# nRF52840_qfaa_var1.net
KiCad netlist of a schematic drawn in EAGLE
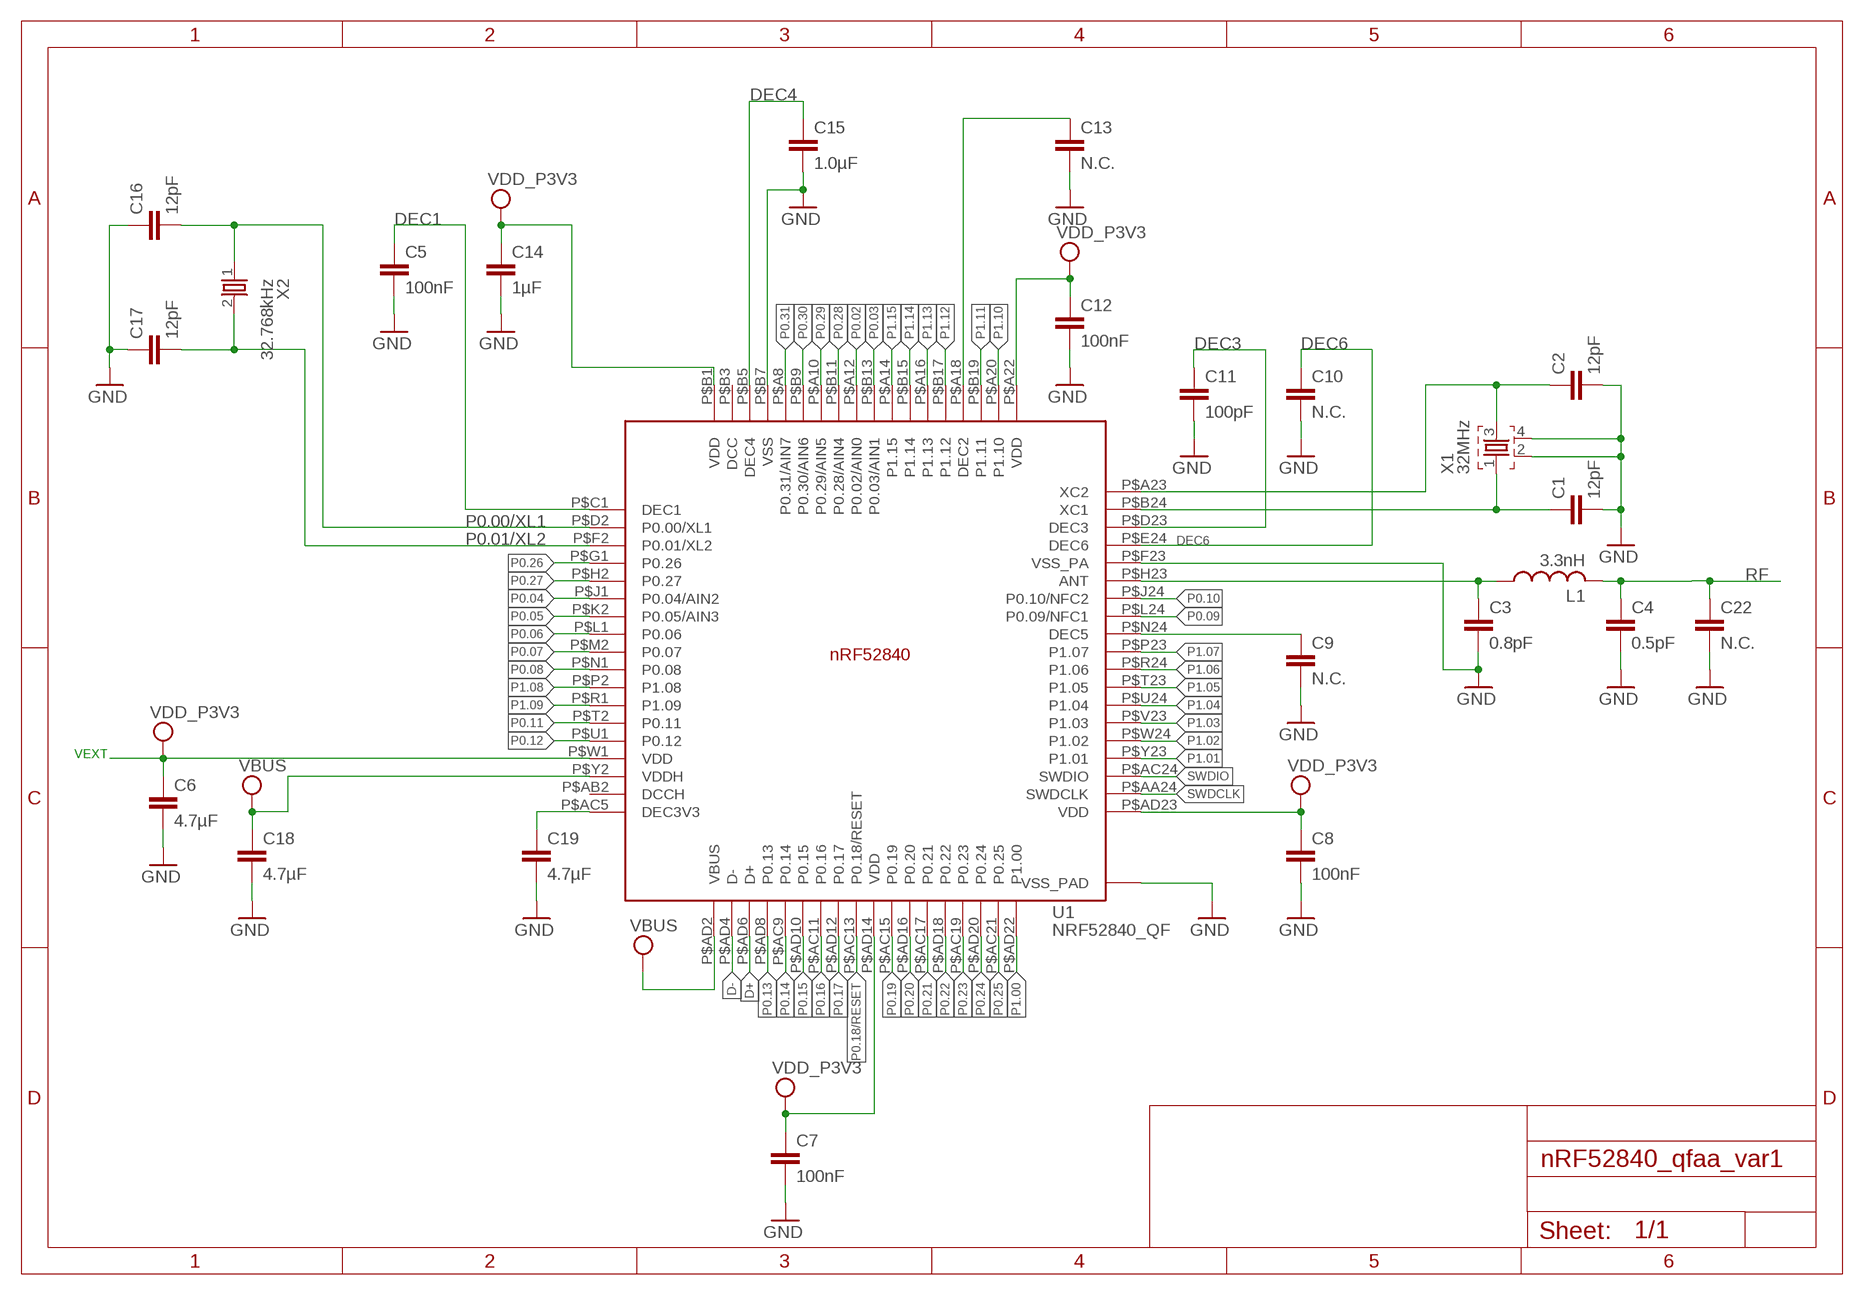
[diagram p0: schematic, sheet 1]

(export (version "E")
  (design (tool "Eeschema 10.0.6"))
  (components
    (comp (ref "C1")
      (value "12pF")
      (footprint "eagle-import:RESC0402_N")
      (libsource (lib "eagle-import") (part "CAPACITOR_0402_N"))
    )
    (comp (ref "C2")
      (value "12pF")
      (footprint "eagle-import:RESC0402_N")
      (libsource (lib "eagle-import") (part "CAPACITOR_0402_N"))
    )
    (comp (ref "C3")
      (value "0.8pF")
      (footprint "eagle-import:RESC0402_N")
      (libsource (lib "eagle-import") (part "CAPACITOR_0402_N"))
    )
    (comp (ref "C4")
      (value "0.5pF")
      (footprint "eagle-import:RESC0402_N")
      (libsource (lib "eagle-import") (part "CAPACITOR_0402_N"))
    )
    (comp (ref "C5")
      (value "100nF")
      (footprint "eagle-import:RESC0402_N")
      (libsource (lib "eagle-import") (part "CAPACITOR_0402_N"))
    )
    (comp (ref "C6")
      (value "4.7µF")
      (footprint "eagle-import:RESC0603_N")
      (libsource (lib "eagle-import") (part "CAPACITOR_0603_N"))
    )
    (comp (ref "C7")
      (value "100nF")
      (footprint "eagle-import:RESC0402_N")
      (libsource (lib "eagle-import") (part "CAPACITOR_0402_N"))
    )
    (comp (ref "C8")
      (value "100nF")
      (footprint "eagle-import:RESC0402_N")
      (libsource (lib "eagle-import") (part "CAPACITOR_0402_N"))
    )
    (comp (ref "C9")
      (value "N.C.")
      (footprint "eagle-import:RESC0402_N")
      (libsource (lib "eagle-import") (part "CAPACITOR_0402_N"))
    )
    (comp (ref "C10")
      (value "N.C.")
      (footprint "eagle-import:RESC0402_N")
      (libsource (lib "eagle-import") (part "CAPACITOR_0402_N"))
    )
    (comp (ref "C11")
      (value "100pF")
      (footprint "eagle-import:RESC0402_N")
      (libsource (lib "eagle-import") (part "CAPACITOR_0402_N"))
    )
    (comp (ref "C12")
      (value "100nF")
      (footprint "eagle-import:RESC0402_N")
      (libsource (lib "eagle-import") (part "CAPACITOR_0402_N"))
    )
    (comp (ref "C13")
      (value "N.C.")
      (footprint "eagle-import:RESC0402_N")
      (libsource (lib "eagle-import") (part "CAPACITOR_0402_N"))
    )
    (comp (ref "C14")
      (value "1µF")
      (footprint "eagle-import:RESC0603_N")
      (libsource (lib "eagle-import") (part "CAPACITOR_0603_N"))
    )
    (comp (ref "C15")
      (value "1.0µF")
      (footprint "eagle-import:RESC0603_N")
      (libsource (lib "eagle-import") (part "CAPACITOR_0603_N"))
    )
    (comp (ref "C16")
      (value "12pF")
      (footprint "eagle-import:RESC0402_N")
      (libsource (lib "eagle-import") (part "CAPACITOR_0402_N"))
    )
    (comp (ref "C17")
      (value "12pF")
      (footprint "eagle-import:RESC0402_N")
      (libsource (lib "eagle-import") (part "CAPACITOR_0402_N"))
    )
    (comp (ref "C18")
      (value "4.7µF")
      (footprint "eagle-import:RESC0603_N")
      (libsource (lib "eagle-import") (part "CAPACITOR_0603_N"))
    )
    (comp (ref "C19")
      (value "4.7µF")
      (footprint "eagle-import:RESC0603_N")
      (libsource (lib "eagle-import") (part "CAPACITOR_0603_N"))
    )
    (comp (ref "C22")
      (value "N.C.")
      (footprint "eagle-import:RESC0402_N")
      (libsource (lib "eagle-import") (part "CAPACITOR_0402_N"))
    )
    (comp (ref "L1")
      (value "3.3nH")
      (footprint "eagle-import:RESC0402_N")
      (libsource (lib "eagle-import") (part "INDUCTOR_0402_N"))
    )
    (comp (ref "U1")
      (value "NRF52840_QF")
      (footprint "eagle-import:AQFN50P700X700X85_HS-74N")
      (libsource (lib "eagle-import") (part "NRF52840_QF"))
    )
    (comp (ref "X1")
      (value "32MHz")
      (footprint "eagle-import:BT-XTAL_2016_N")
      (libsource (lib "eagle-import") (part "XTAL_32MHZ"))
    )
    (comp (ref "X2")
      (value "32.768kHz")
      (footprint "eagle-import:XTAL_3215_N")
      (libsource (lib "eagle-import") (part "XTAL_32KHZ"))
    )
  )
  (nets
    (net (code "1") (name "/DEC1") (class "Default")
      (node (ref "C5") (pin "1") (pinfunction "1_1") (pintype "passive"))
      (node (ref "U1") (pin "P$C1") (pinfunction "DEC1_P$C1") (pintype "power_in"))
    )
    (net (code "2") (name "/DEC3") (class "Default")
      (node (ref "C11") (pin "1") (pinfunction "1_1") (pintype "passive"))
      (node (ref "U1") (pin "P$D23") (pinfunction "DEC3_P$D23") (pintype "bidirectional"))
    )
    (net (code "3") (name "/DEC4") (class "Default")
      (node (ref "C15") (pin "1") (pinfunction "1_1") (pintype "passive"))
      (node (ref "U1") (pin "P$B5") (pinfunction "DEC4_P$B5") (pintype "power_in"))
    )
    (net (code "4") (name "/DEC6") (class "Default")
      (node (ref "C10") (pin "1") (pinfunction "1_1") (pintype "passive"))
      (node (ref "U1") (pin "P$E24") (pinfunction "DEC6_P$E24") (pintype "bidirectional"))
    )
    (net (code "5") (name "/P0.00{slash}XL1") (class "Default")
      (node (ref "C16") (pin "2") (pinfunction "2_2") (pintype "passive"))
      (node (ref "U1") (pin "P$D2") (pinfunction "P0.00/XL1_P$D2") (pintype "bidirectional"))
      (node (ref "X2") (pin "1") (pinfunction "1_1") (pintype "passive"))
    )
    (net (code "6") (name "/P0.01{slash}XL2") (class "Default")
      (node (ref "C17") (pin "2") (pinfunction "2_2") (pintype "passive"))
      (node (ref "U1") (pin "P$F2") (pinfunction "P0.01/XL2_P$F2") (pintype "bidirectional"))
      (node (ref "X2") (pin "2") (pinfunction "2_2") (pintype "passive"))
    )
    (net (code "7") (name "/RF") (class "Default")
      (node (ref "C22") (pin "1") (pinfunction "1_1") (pintype "passive"))
      (node (ref "C4") (pin "1") (pinfunction "1_1") (pintype "passive"))
      (node (ref "L1") (pin "2") (pinfunction "2_2") (pintype "passive"))
    )
    (net (code "8") (name "D+") (class "Default")
      (node (ref "U1") (pin "P$AD6") (pinfunction "D+_P$AD6") (pintype "bidirectional"))
    )
    (net (code "9") (name "D-") (class "Default")
      (node (ref "U1") (pin "P$AD4") (pinfunction "D-_P$AD4") (pintype "bidirectional"))
    )
    (net (code "10") (name "GND") (class "Default")
      (node (ref "C1") (pin "2") (pinfunction "2_2") (pintype "passive"))
      (node (ref "C10") (pin "2") (pinfunction "2_2") (pintype "passive"))
      (node (ref "C11") (pin "2") (pinfunction "2_2") (pintype "passive"))
      (node (ref "C12") (pin "2") (pinfunction "2_2") (pintype "passive"))
      (node (ref "C13") (pin "2") (pinfunction "2_2") (pintype "passive"))
      (node (ref "C14") (pin "2") (pinfunction "2_2") (pintype "passive"))
      (node (ref "C15") (pin "2") (pinfunction "2_2") (pintype "passive"))
      (node (ref "C16") (pin "1") (pinfunction "1_1") (pintype "passive"))
      (node (ref "C17") (pin "1") (pinfunction "1_1") (pintype "passive"))
      (node (ref "C18") (pin "2") (pinfunction "2_2") (pintype "passive"))
      (node (ref "C19") (pin "2") (pinfunction "2_2") (pintype "passive"))
      (node (ref "C2") (pin "2") (pinfunction "2_2") (pintype "passive"))
      (node (ref "C22") (pin "2") (pinfunction "2_2") (pintype "passive"))
      (node (ref "C3") (pin "2") (pinfunction "2_2") (pintype "passive"))
      (node (ref "C4") (pin "2") (pinfunction "2_2") (pintype "passive"))
      (node (ref "C5") (pin "2") (pinfunction "2_2") (pintype "passive"))
      (node (ref "C6") (pin "2") (pinfunction "2_2") (pintype "passive"))
      (node (ref "C7") (pin "2") (pinfunction "2_2") (pintype "passive"))
      (node (ref "C8") (pin "2") (pinfunction "2_2") (pintype "passive"))
      (node (ref "C9") (pin "2") (pinfunction "2_2") (pintype "passive"))
      (node (ref "U1") (pin "P$74") (pinfunction "VSS_PAD_P$74") (pintype "bidirectional"))
      (node (ref "U1") (pin "P$75") (pinfunction "VSS_PAD_P$75") (pintype "bidirectional"))
      (node (ref "U1") (pin "P$76") (pinfunction "VSS_PAD_P$76") (pintype "bidirectional"))
      (node (ref "U1") (pin "P$77") (pinfunction "VSS_PAD_P$77") (pintype "bidirectional"))
      (node (ref "U1") (pin "P$78") (pinfunction "VSS_PAD_P$78") (pintype "bidirectional"))
      (node (ref "U1") (pin "P$79") (pinfunction "VSS_PAD_P$79") (pintype "bidirectional"))
      (node (ref "U1") (pin "P$80") (pinfunction "VSS_PAD_P$80") (pintype "bidirectional"))
      (node (ref "U1") (pin "P$81") (pinfunction "VSS_PAD_P$81") (pintype "bidirectional"))
      (node (ref "U1") (pin "P$82") (pinfunction "VSS_PAD_P$82") (pintype "bidirectional"))
      (node (ref "U1") (pin "P$83") (pinfunction "VSS_PAD_P$83") (pintype "bidirectional"))
      (node (ref "U1") (pin "P$84") (pinfunction "VSS_PAD_P$84") (pintype "bidirectional"))
      (node (ref "U1") (pin "P$85") (pinfunction "VSS_PAD_P$85") (pintype "bidirectional"))
      (node (ref "U1") (pin "P$86") (pinfunction "VSS_PAD_P$86") (pintype "bidirectional"))
      (node (ref "U1") (pin "P$87") (pinfunction "VSS_PAD_P$87") (pintype "bidirectional"))
      (node (ref "U1") (pin "P$88") (pinfunction "VSS_PAD_P$88") (pintype "bidirectional"))
      (node (ref "U1") (pin "P$89") (pinfunction "VSS_PAD_P$89") (pintype "bidirectional"))
      (node (ref "U1") (pin "P$90") (pinfunction "VSS_PAD_P$90") (pintype "bidirectional"))
      (node (ref "U1") (pin "P$B7") (pinfunction "VSS_P$B7") (pintype "power_in"))
      (node (ref "U1") (pin "P$F23") (pinfunction "VSS_PA_P$F23") (pintype "bidirectional"))
      (node (ref "X1") (pin "2") (pinfunction "2_2") (pintype "passive"))
      (node (ref "X1") (pin "4") (pinfunction "4_4") (pintype "passive"))
    )
    (net (code "11") (name "Net-(U1-ANT)") (class "Default")
      (node (ref "C3") (pin "1") (pinfunction "1_1") (pintype "passive"))
      (node (ref "L1") (pin "1") (pinfunction "1_1") (pintype "passive"))
      (node (ref "U1") (pin "P$H23") (pinfunction "ANT_P$H23") (pintype "bidirectional"))
    )
    (net (code "12") (name "Net-(U1-DEC2)") (class "Default")
      (node (ref "C13") (pin "1") (pinfunction "1_1") (pintype "passive"))
      (node (ref "U1") (pin "P$A18") (pinfunction "DEC2_P$A18") (pintype "bidirectional"))
    )
    (net (code "13") (name "Net-(U1-DEC3V3)") (class "Default")
      (node (ref "C19") (pin "1") (pinfunction "1_1") (pintype "passive"))
      (node (ref "U1") (pin "P$AC5") (pinfunction "DEC3V3_P$AC5") (pintype "bidirectional"))
    )
    (net (code "14") (name "Net-(U1-DEC5)") (class "Default")
      (node (ref "C9") (pin "1") (pinfunction "1_1") (pintype "passive"))
      (node (ref "U1") (pin "P$N24") (pinfunction "DEC5_P$N24") (pintype "bidirectional"))
    )
    (net (code "15") (name "Net-(U1-XC1)") (class "Default")
      (node (ref "C1") (pin "1") (pinfunction "1_1") (pintype "passive"))
      (node (ref "U1") (pin "P$B24") (pinfunction "XC1_P$B24") (pintype "input"))
      (node (ref "X1") (pin "1") (pinfunction "1_1") (pintype "passive"))
    )
    (net (code "16") (name "Net-(U1-XC2)") (class "Default")
      (node (ref "C2") (pin "1") (pinfunction "1_1") (pintype "passive"))
      (node (ref "U1") (pin "P$A23") (pinfunction "XC2_P$A23") (pintype "output"))
      (node (ref "X1") (pin "3") (pinfunction "3_3") (pintype "passive"))
    )
    (net (code "17") (name "P0.02") (class "Default")
      (node (ref "U1") (pin "P$A12") (pinfunction "P0.02/AIN0_P$A12") (pintype "bidirectional"))
    )
    (net (code "18") (name "P0.03") (class "Default")
      (node (ref "U1") (pin "P$B13") (pinfunction "P0.03/AIN1_P$B13") (pintype "bidirectional"))
    )
    (net (code "19") (name "P0.04") (class "Default")
      (node (ref "U1") (pin "P$J1") (pinfunction "P0.04/AIN2_P$J1") (pintype "bidirectional"))
    )
    (net (code "20") (name "P0.05") (class "Default")
      (node (ref "U1") (pin "P$K2") (pinfunction "P0.05/AIN3_P$K2") (pintype "bidirectional"))
    )
    (net (code "21") (name "P0.06") (class "Default")
      (node (ref "U1") (pin "P$L1") (pinfunction "P0.06_P$L1") (pintype "bidirectional"))
    )
    (net (code "22") (name "P0.07") (class "Default")
      (node (ref "U1") (pin "P$M2") (pinfunction "P0.07_P$M2") (pintype "bidirectional"))
    )
    (net (code "23") (name "P0.08") (class "Default")
      (node (ref "U1") (pin "P$N1") (pinfunction "P0.08_P$N1") (pintype "bidirectional"))
    )
    (net (code "24") (name "P0.09") (class "Default")
      (node (ref "U1") (pin "P$L24") (pinfunction "P0.09/NFC1_P$L24") (pintype "bidirectional"))
    )
    (net (code "25") (name "P0.10") (class "Default")
      (node (ref "U1") (pin "P$J24") (pinfunction "P0.10/NFC2_P$J24") (pintype "bidirectional"))
    )
    (net (code "26") (name "P0.11") (class "Default")
      (node (ref "U1") (pin "P$T2") (pinfunction "P0.11_P$T2") (pintype "bidirectional"))
    )
    (net (code "27") (name "P0.12") (class "Default")
      (node (ref "U1") (pin "P$U1") (pinfunction "P0.12_P$U1") (pintype "bidirectional"))
    )
    (net (code "28") (name "P0.13") (class "Default")
      (node (ref "U1") (pin "P$AD8") (pinfunction "P0.13_P$AD8") (pintype "bidirectional"))
    )
    (net (code "29") (name "P0.14") (class "Default")
      (node (ref "U1") (pin "P$AC9") (pinfunction "P0.14_P$AC9") (pintype "bidirectional"))
    )
    (net (code "30") (name "P0.15") (class "Default")
      (node (ref "U1") (pin "P$AD10") (pinfunction "P0.15_P$AD10") (pintype "bidirectional"))
    )
    (net (code "31") (name "P0.16") (class "Default")
      (node (ref "U1") (pin "P$AC11") (pinfunction "P0.16_P$AC11") (pintype "bidirectional"))
    )
    (net (code "32") (name "P0.17") (class "Default")
      (node (ref "U1") (pin "P$AD12") (pinfunction "P0.17_P$AD12") (pintype "bidirectional"))
    )
    (net (code "33") (name "P0.18{slash}RESET") (class "Default")
      (node (ref "U1") (pin "P$AC13") (pinfunction "P0.18/RESET_P$AC13") (pintype "bidirectional"))
    )
    (net (code "34") (name "P0.19") (class "Default")
      (node (ref "U1") (pin "P$AC15") (pinfunction "P0.19_P$AC15") (pintype "bidirectional"))
    )
    (net (code "35") (name "P0.20") (class "Default")
      (node (ref "U1") (pin "P$AD16") (pinfunction "P0.20_P$AD16") (pintype "bidirectional"))
    )
    (net (code "36") (name "P0.21") (class "Default")
      (node (ref "U1") (pin "P$AC17") (pinfunction "P0.21_P$AC17") (pintype "bidirectional"))
    )
    (net (code "37") (name "P0.22") (class "Default")
      (node (ref "U1") (pin "P$AD18") (pinfunction "P0.22_P$AD18") (pintype "bidirectional"))
    )
    (net (code "38") (name "P0.23") (class "Default")
      (node (ref "U1") (pin "P$AC19") (pinfunction "P0.23_P$AC19") (pintype "bidirectional"))
    )
    (net (code "39") (name "P0.24") (class "Default")
      (node (ref "U1") (pin "P$AD20") (pinfunction "P0.24_P$AD20") (pintype "bidirectional"))
    )
    (net (code "40") (name "P0.25") (class "Default")
      (node (ref "U1") (pin "P$AC21") (pinfunction "P0.25_P$AC21") (pintype "bidirectional"))
    )
    (net (code "41") (name "P0.26") (class "Default")
      (node (ref "U1") (pin "P$G1") (pinfunction "P0.26_P$G1") (pintype "bidirectional"))
    )
    (net (code "42") (name "P0.27") (class "Default")
      (node (ref "U1") (pin "P$H2") (pinfunction "P0.27_P$H2") (pintype "bidirectional"))
    )
    (net (code "43") (name "P0.28") (class "Default")
      (node (ref "U1") (pin "P$B11") (pinfunction "P0.28/AIN4_P$B11") (pintype "bidirectional"))
    )
    (net (code "44") (name "P0.29") (class "Default")
      (node (ref "U1") (pin "P$A10") (pinfunction "P0.29/AIN5_P$A10") (pintype "bidirectional"))
    )
    (net (code "45") (name "P0.30") (class "Default")
      (node (ref "U1") (pin "P$B9") (pinfunction "P0.30/AIN6_P$B9") (pintype "bidirectional"))
    )
    (net (code "46") (name "P0.31") (class "Default")
      (node (ref "U1") (pin "P$A8") (pinfunction "P0.31/AIN7_P$A8") (pintype "bidirectional"))
    )
    (net (code "47") (name "P1.00") (class "Default")
      (node (ref "U1") (pin "P$AD22") (pinfunction "P1.00_P$AD22") (pintype "bidirectional"))
    )
    (net (code "48") (name "P1.01") (class "Default")
      (node (ref "U1") (pin "P$Y23") (pinfunction "P1.01_P$Y23") (pintype "bidirectional"))
    )
    (net (code "49") (name "P1.02") (class "Default")
      (node (ref "U1") (pin "P$W24") (pinfunction "P1.02_P$W24") (pintype "bidirectional"))
    )
    (net (code "50") (name "P1.03") (class "Default")
      (node (ref "U1") (pin "P$V23") (pinfunction "P1.03_P$V23") (pintype "bidirectional"))
    )
    (net (code "51") (name "P1.04") (class "Default")
      (node (ref "U1") (pin "P$U24") (pinfunction "P1.04_P$U24") (pintype "bidirectional"))
    )
    (net (code "52") (name "P1.05") (class "Default")
      (node (ref "U1") (pin "P$T23") (pinfunction "P1.05_P$T23") (pintype "bidirectional"))
    )
    (net (code "53") (name "P1.06") (class "Default")
      (node (ref "U1") (pin "P$R24") (pinfunction "P1.06_P$R24") (pintype "bidirectional"))
    )
    (net (code "54") (name "P1.07") (class "Default")
      (node (ref "U1") (pin "P$P23") (pinfunction "P1.07_P$P23") (pintype "bidirectional"))
    )
    (net (code "55") (name "P1.08") (class "Default")
      (node (ref "U1") (pin "P$P2") (pinfunction "P1.08_P$P2") (pintype "bidirectional"))
    )
    (net (code "56") (name "P1.09") (class "Default")
      (node (ref "U1") (pin "P$R1") (pinfunction "P1.09_P$R1") (pintype "bidirectional"))
    )
    (net (code "57") (name "P1.10") (class "Default")
      (node (ref "U1") (pin "P$A20") (pinfunction "P1.10_P$A20") (pintype "bidirectional"))
    )
    (net (code "58") (name "P1.11") (class "Default")
      (node (ref "U1") (pin "P$B19") (pinfunction "P1.11_P$B19") (pintype "bidirectional"))
    )
    (net (code "59") (name "P1.12") (class "Default")
      (node (ref "U1") (pin "P$B17") (pinfunction "P1.12_P$B17") (pintype "bidirectional"))
    )
    (net (code "60") (name "P1.13") (class "Default")
      (node (ref "U1") (pin "P$A16") (pinfunction "P1.13_P$A16") (pintype "bidirectional"))
    )
    (net (code "61") (name "P1.14") (class "Default")
      (node (ref "U1") (pin "P$B15") (pinfunction "P1.14_P$B15") (pintype "bidirectional"))
    )
    (net (code "62") (name "P1.15") (class "Default")
      (node (ref "U1") (pin "P$A14") (pinfunction "P1.15_P$A14") (pintype "bidirectional"))
    )
    (net (code "63") (name "SWDCLK") (class "Default")
      (node (ref "U1") (pin "P$AA24") (pinfunction "SWDCLK_P$AA24") (pintype "input"))
    )
    (net (code "64") (name "SWDIO") (class "Default")
      (node (ref "U1") (pin "P$AC24") (pinfunction "SWDIO_P$AC24") (pintype "bidirectional"))
    )
    (net (code "65") (name "VBUS") (class "Default")
      (node (ref "C18") (pin "1") (pinfunction "1_1") (pintype "passive"))
      (node (ref "U1") (pin "P$AD2") (pinfunction "VBUS_P$AD2") (pintype "power_in"))
      (node (ref "U1") (pin "P$Y2") (pinfunction "VDDH_P$Y2") (pintype "power_in"))
    )
    (net (code "66") (name "VDD_P3V3") (class "Default")
      (node (ref "C12") (pin "1") (pinfunction "1_1") (pintype "passive"))
      (node (ref "C14") (pin "1") (pinfunction "1_1") (pintype "passive"))
      (node (ref "C6") (pin "1") (pinfunction "1_1") (pintype "passive"))
      (node (ref "C7") (pin "1") (pinfunction "1_1") (pintype "passive"))
      (node (ref "C8") (pin "1") (pinfunction "1_1") (pintype "passive"))
      (node (ref "U1") (pin "P$A22") (pinfunction "VDD_P$A22") (pintype "power_in"))
      (node (ref "U1") (pin "P$AD14") (pinfunction "VDD_P$AD14") (pintype "power_in"))
      (node (ref "U1") (pin "P$AD23") (pinfunction "VDD_P$AD23") (pintype "power_in"))
      (node (ref "U1") (pin "P$B1") (pinfunction "VDD_P$B1") (pintype "power_in"))
      (node (ref "U1") (pin "P$W1") (pinfunction "VDD_P$W1") (pintype "power_in"))
    )
    (net (code "67") (name "unconnected-(U1-DCC-PadP$B3)") (class "Default")
      (node (ref "U1") (pin "P$B3") (pinfunction "DCC_P$B3") (pintype "output"))
    )
    (net (code "68") (name "unconnected-(U1-DCCH-PadP$AB2)") (class "Default")
      (node (ref "U1") (pin "P$AB2") (pinfunction "DCCH_P$AB2") (pintype "bidirectional"))
    )
  )
)
